# design.net
KiCad netlist of a schematic drawn in Altium Designer
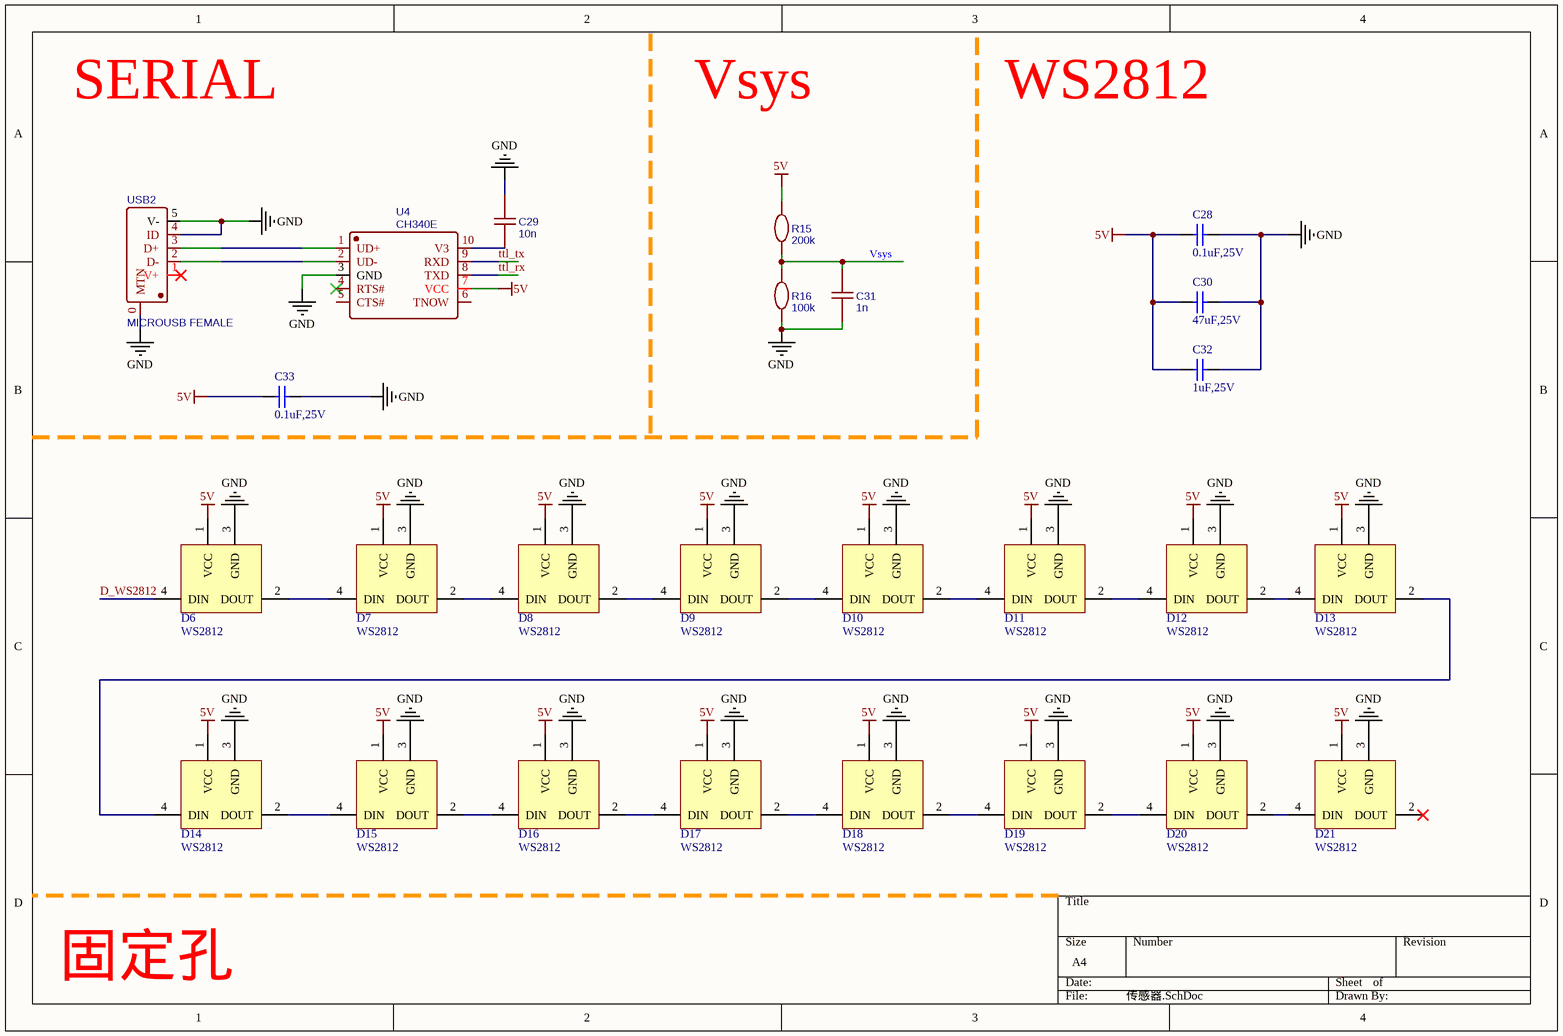
[diagram p0: 传感器.SchDoc]

(export (version "E")
  (design (tool "Eeschema 10.0.6"))
  (components
    (comp (ref "C28")
      (value "0.1uF,25V")
      (footprint "0402_C")
      (description "贴片电容")
      (fields (field (name "PART NUMBER") "T_Cap_0603_0.1uF_25V_X5R") (field (name "TOLERANCE") "10%"))
      (libsource (lib "Database_Library") (part "Cap"))
    )
    (comp (ref "C29")
      (value "10n")
      (footprint "0402_C")
      (fields (field (name "CONTRIBUTOR") "LCEDA_Lib"))
      (libsource (lib "altium-import") (part "root_1_10n_"))
    )
    (comp (ref "C30")
      (value "47uF,25V")
      (footprint "0402_C")
      (description "贴片电容")
      (fields (field (name "PART NUMBER") "T_Cap_0603_0.1uF_25V_X5R") (field (name "TOLERANCE") "10%"))
      (libsource (lib "Database_Library") (part "Cap"))
    )
    (comp (ref "C31")
      (value "1n")
      (footprint "0402_C")
      (fields (field (name "CONTRIBUTOR") "LCEDA_Lib"))
      (libsource (lib "altium-import") (part "root_1_1n_"))
    )
    (comp (ref "C32")
      (value "1uF,25V")
      (footprint "0402_C")
      (description "贴片电容")
      (fields (field (name "PART NUMBER") "T_Cap_0603_0.1uF_25V_X5R") (field (name "TOLERANCE") "10%"))
      (libsource (lib "Database_Library") (part "Cap"))
    )
    (comp (ref "C33")
      (value "0.1uF,25V")
      (footprint "0402_C")
      (description "贴片电容")
      (fields (field (name "PART NUMBER") "T_Cap_0603_0.1uF_25V_X5R") (field (name "TOLERANCE") "10%"))
      (libsource (lib "Database_Library") (part "Cap"))
    )
    (comp (ref "D6")
      (value "WS2812")
      (footprint "LED-SMD_4P-L3.5-W3.5-TL_WS2812B")
      (libsource (lib "Schlib_PICO") (part "WS2812"))
    )
    (comp (ref "D7")
      (value "WS2812")
      (footprint "LED-SMD_4P-L3.5-W3.5-TL_WS2812B")
      (libsource (lib "Schlib_PICO") (part "WS2812"))
    )
    (comp (ref "D8")
      (value "WS2812")
      (footprint "LED-SMD_4P-L3.5-W3.5-TL_WS2812B")
      (libsource (lib "Schlib_PICO") (part "WS2812"))
    )
    (comp (ref "D9")
      (value "WS2812")
      (footprint "LED-SMD_4P-L3.5-W3.5-TL_WS2812B")
      (libsource (lib "Schlib_PICO") (part "WS2812"))
    )
    (comp (ref "D10")
      (value "WS2812")
      (footprint "LED-SMD_4P-L3.5-W3.5-TL_WS2812B")
      (libsource (lib "Schlib_PICO") (part "WS2812"))
    )
    (comp (ref "D11")
      (value "WS2812")
      (footprint "LED-SMD_4P-L3.5-W3.5-TL_WS2812B")
      (libsource (lib "Schlib_PICO") (part "WS2812"))
    )
    (comp (ref "D12")
      (value "WS2812")
      (footprint "LED-SMD_4P-L3.5-W3.5-TL_WS2812B")
      (libsource (lib "Schlib_PICO") (part "WS2812"))
    )
    (comp (ref "D13")
      (value "WS2812")
      (footprint "LED-SMD_4P-L3.5-W3.5-TL_WS2812B")
      (libsource (lib "Schlib_PICO") (part "WS2812"))
    )
    (comp (ref "D14")
      (value "WS2812")
      (footprint "LED-SMD_4P-L3.5-W3.5-TL_WS2812B")
      (libsource (lib "Schlib_PICO") (part "WS2812"))
    )
    (comp (ref "D15")
      (value "WS2812")
      (footprint "LED-SMD_4P-L3.5-W3.5-TL_WS2812B")
      (libsource (lib "Schlib_PICO") (part "WS2812"))
    )
    (comp (ref "D16")
      (value "WS2812")
      (footprint "LED-SMD_4P-L3.5-W3.5-TL_WS2812B")
      (libsource (lib "Schlib_PICO") (part "WS2812"))
    )
    (comp (ref "D17")
      (value "WS2812")
      (footprint "LED-SMD_4P-L3.5-W3.5-TL_WS2812B")
      (libsource (lib "Schlib_PICO") (part "WS2812"))
    )
    (comp (ref "D18")
      (value "WS2812")
      (footprint "LED-SMD_4P-L3.5-W3.5-TL_WS2812B")
      (libsource (lib "Schlib_PICO") (part "WS2812"))
    )
    (comp (ref "D19")
      (value "WS2812")
      (footprint "LED-SMD_4P-L3.5-W3.5-TL_WS2812B")
      (libsource (lib "Schlib_PICO") (part "WS2812"))
    )
    (comp (ref "D20")
      (value "WS2812")
      (footprint "LED-SMD_4P-L3.5-W3.5-TL_WS2812B")
      (libsource (lib "Schlib_PICO") (part "WS2812"))
    )
    (comp (ref "D21")
      (value "WS2812")
      (footprint "LED-SMD_4P-L3.5-W3.5-TL_WS2812B")
      (libsource (lib "Schlib_PICO") (part "WS2812"))
    )
    (comp (ref "R15")
      (value "200k")
      (footprint "0402_R")
      (fields (field (name "CONTRIBUTOR") "LCEDA_Lib"))
      (libsource (lib "altium-import") (part "root_1_200k_"))
    )
    (comp (ref "R16")
      (value "100k")
      (footprint "0402_R")
      (fields (field (name "CONTRIBUTOR") "LCEDA_Lib"))
      (libsource (lib "altium-import") (part "root_1_100k_"))
    )
    (comp (ref "U4")
      (value "CH340E")
      (footprint "MSOP-10_L3.0-W3.0-P0.50-LS5.0-BL")
      (fields (field (name "BOM_SUPPLIER PART") "C99652"))
      (libsource (lib "altium-import") (part "root_0_CH340E_"))
    )
    (comp (ref "USB2")
      (value "MICROUSB FEMALE")
      (footprint "USB-B/S_A")
      (fields
        (field (name "BOM_MANUFACTURER PART") "micro USBFemale")
        (field (name "BOM_SUPPLIER PART") "C10418")
      )
      (libsource (lib "altium-import") (part "root_0_mirrored_MICROUSB FEMALE_"))
    )
  )
  (nets
    (net (code "1") (name "/D_WS2812") (class "Default")
      (node (ref "D6") (pin "4") (pinfunction "DIN_4") (pintype "passive"))
    )
    (net (code "2") (name "/Vsys") (class "Default")
      (node (ref "C31") (pin "2") (pinfunction "2_2") (pintype "passive"))
      (node (ref "R15") (pin "1") (pinfunction "1_1") (pintype "passive"))
      (node (ref "R16") (pin "2") (pinfunction "2_2") (pintype "passive"))
    )
    (net (code "3") (name "/ttl_rx") (class "Default")
      (node (ref "U4") (pin "8") (pinfunction "TXD_8") (pintype "passive"))
    )
    (net (code "4") (name "/ttl_tx") (class "Default")
      (node (ref "U4") (pin "9") (pinfunction "RXD_9") (pintype "passive"))
    )
    (net (code "5") (name "5V") (class "Default")
      (node (ref "C28") (pin "2") (pinfunction "2_2") (pintype "passive"))
      (node (ref "C30") (pin "2") (pinfunction "2_2") (pintype "passive"))
      (node (ref "C32") (pin "2") (pinfunction "2_2") (pintype "passive"))
      (node (ref "C33") (pin "2") (pinfunction "2_2") (pintype "passive"))
      (node (ref "D10") (pin "1") (pinfunction "VCC_1") (pintype "passive"))
      (node (ref "D11") (pin "1") (pinfunction "VCC_1") (pintype "passive"))
      (node (ref "D12") (pin "1") (pinfunction "VCC_1") (pintype "passive"))
      (node (ref "D13") (pin "1") (pinfunction "VCC_1") (pintype "passive"))
      (node (ref "D14") (pin "1") (pinfunction "VCC_1") (pintype "passive"))
      (node (ref "D15") (pin "1") (pinfunction "VCC_1") (pintype "passive"))
      (node (ref "D16") (pin "1") (pinfunction "VCC_1") (pintype "passive"))
      (node (ref "D17") (pin "1") (pinfunction "VCC_1") (pintype "passive"))
      (node (ref "D18") (pin "1") (pinfunction "VCC_1") (pintype "passive"))
      (node (ref "D19") (pin "1") (pinfunction "VCC_1") (pintype "passive"))
      (node (ref "D20") (pin "1") (pinfunction "VCC_1") (pintype "passive"))
      (node (ref "D21") (pin "1") (pinfunction "VCC_1") (pintype "passive"))
      (node (ref "D6") (pin "1") (pinfunction "VCC_1") (pintype "passive"))
      (node (ref "D7") (pin "1") (pinfunction "VCC_1") (pintype "passive"))
      (node (ref "D8") (pin "1") (pinfunction "VCC_1") (pintype "passive"))
      (node (ref "D9") (pin "1") (pinfunction "VCC_1") (pintype "passive"))
      (node (ref "R15") (pin "2") (pinfunction "2_2") (pintype "passive"))
      (node (ref "U4") (pin "7") (pinfunction "VCC_7") (pintype "passive"))
    )
    (net (code "6") (name "GND") (class "Default")
      (node (ref "C28") (pin "1") (pinfunction "1_1") (pintype "passive"))
      (node (ref "C29") (pin "2") (pinfunction "2_2") (pintype "passive"))
      (node (ref "C30") (pin "1") (pinfunction "1_1") (pintype "passive"))
      (node (ref "C31") (pin "1") (pinfunction "1_1") (pintype "passive"))
      (node (ref "C32") (pin "1") (pinfunction "1_1") (pintype "passive"))
      (node (ref "C33") (pin "1") (pinfunction "1_1") (pintype "passive"))
      (node (ref "D10") (pin "3") (pinfunction "GND_3") (pintype "passive"))
      (node (ref "D11") (pin "3") (pinfunction "GND_3") (pintype "passive"))
      (node (ref "D12") (pin "3") (pinfunction "GND_3") (pintype "passive"))
      (node (ref "D13") (pin "3") (pinfunction "GND_3") (pintype "passive"))
      (node (ref "D14") (pin "3") (pinfunction "GND_3") (pintype "passive"))
      (node (ref "D15") (pin "3") (pinfunction "GND_3") (pintype "passive"))
      (node (ref "D16") (pin "3") (pinfunction "GND_3") (pintype "passive"))
      (node (ref "D17") (pin "3") (pinfunction "GND_3") (pintype "passive"))
      (node (ref "D18") (pin "3") (pinfunction "GND_3") (pintype "passive"))
      (node (ref "D19") (pin "3") (pinfunction "GND_3") (pintype "passive"))
      (node (ref "D20") (pin "3") (pinfunction "GND_3") (pintype "passive"))
      (node (ref "D21") (pin "3") (pinfunction "GND_3") (pintype "passive"))
      (node (ref "D6") (pin "3") (pinfunction "GND_3") (pintype "passive"))
      (node (ref "D7") (pin "3") (pinfunction "GND_3") (pintype "passive"))
      (node (ref "D8") (pin "3") (pinfunction "GND_3") (pintype "passive"))
      (node (ref "D9") (pin "3") (pinfunction "GND_3") (pintype "passive"))
      (node (ref "R16") (pin "1") (pinfunction "1_1") (pintype "passive"))
      (node (ref "U4") (pin "3") (pinfunction "GND_3") (pintype "passive"))
      (node (ref "USB2") (pin "0") (pinfunction "MTN_0") (pintype "passive"))
      (node (ref "USB2") (pin "4") (pinfunction "ID_4") (pintype "passive"))
      (node (ref "USB2") (pin "5") (pinfunction "V-_5") (pintype "passive"))
    )
    (net (code "7") (name "Net-(D6-DOUT)") (class "Default")
      (node (ref "D6") (pin "2") (pinfunction "DOUT_2") (pintype "passive"))
      (node (ref "D7") (pin "4") (pinfunction "DIN_4") (pintype "passive"))
    )
    (net (code "8") (name "Net-(D7-DOUT)") (class "Default")
      (node (ref "D7") (pin "2") (pinfunction "DOUT_2") (pintype "passive"))
      (node (ref "D8") (pin "4") (pinfunction "DIN_4") (pintype "passive"))
    )
    (net (code "9") (name "Net-(D8-DOUT)") (class "Default")
      (node (ref "D8") (pin "2") (pinfunction "DOUT_2") (pintype "passive"))
      (node (ref "D9") (pin "4") (pinfunction "DIN_4") (pintype "passive"))
    )
    (net (code "10") (name "Net-(D10-DIN)") (class "Default")
      (node (ref "D10") (pin "4") (pinfunction "DIN_4") (pintype "passive"))
      (node (ref "D9") (pin "2") (pinfunction "DOUT_2") (pintype "passive"))
    )
    (net (code "11") (name "Net-(D10-DOUT)") (class "Default")
      (node (ref "D10") (pin "2") (pinfunction "DOUT_2") (pintype "passive"))
      (node (ref "D11") (pin "4") (pinfunction "DIN_4") (pintype "passive"))
    )
    (net (code "12") (name "Net-(D11-DOUT)") (class "Default")
      (node (ref "D11") (pin "2") (pinfunction "DOUT_2") (pintype "passive"))
      (node (ref "D12") (pin "4") (pinfunction "DIN_4") (pintype "passive"))
    )
    (net (code "13") (name "Net-(D12-DOUT)") (class "Default")
      (node (ref "D12") (pin "2") (pinfunction "DOUT_2") (pintype "passive"))
      (node (ref "D13") (pin "4") (pinfunction "DIN_4") (pintype "passive"))
    )
    (net (code "14") (name "Net-(D13-DOUT)") (class "Default")
      (node (ref "D13") (pin "2") (pinfunction "DOUT_2") (pintype "passive"))
      (node (ref "D14") (pin "4") (pinfunction "DIN_4") (pintype "passive"))
    )
    (net (code "15") (name "Net-(D14-DOUT)") (class "Default")
      (node (ref "D14") (pin "2") (pinfunction "DOUT_2") (pintype "passive"))
      (node (ref "D15") (pin "4") (pinfunction "DIN_4") (pintype "passive"))
    )
    (net (code "16") (name "Net-(D15-DOUT)") (class "Default")
      (node (ref "D15") (pin "2") (pinfunction "DOUT_2") (pintype "passive"))
      (node (ref "D16") (pin "4") (pinfunction "DIN_4") (pintype "passive"))
    )
    (net (code "17") (name "Net-(D16-DOUT)") (class "Default")
      (node (ref "D16") (pin "2") (pinfunction "DOUT_2") (pintype "passive"))
      (node (ref "D17") (pin "4") (pinfunction "DIN_4") (pintype "passive"))
    )
    (net (code "18") (name "Net-(D17-DOUT)") (class "Default")
      (node (ref "D17") (pin "2") (pinfunction "DOUT_2") (pintype "passive"))
      (node (ref "D18") (pin "4") (pinfunction "DIN_4") (pintype "passive"))
    )
    (net (code "19") (name "Net-(D18-DOUT)") (class "Default")
      (node (ref "D18") (pin "2") (pinfunction "DOUT_2") (pintype "passive"))
      (node (ref "D19") (pin "4") (pinfunction "DIN_4") (pintype "passive"))
    )
    (net (code "20") (name "Net-(D19-DOUT)") (class "Default")
      (node (ref "D19") (pin "2") (pinfunction "DOUT_2") (pintype "passive"))
      (node (ref "D20") (pin "4") (pinfunction "DIN_4") (pintype "passive"))
    )
    (net (code "21") (name "Net-(D20-DOUT)") (class "Default")
      (node (ref "D20") (pin "2") (pinfunction "DOUT_2") (pintype "passive"))
      (node (ref "D21") (pin "4") (pinfunction "DIN_4") (pintype "passive"))
    )
    (net (code "22") (name "Net-(U4-UD+)") (class "Default")
      (node (ref "U4") (pin "1") (pinfunction "UD+_1") (pintype "passive"))
      (node (ref "USB2") (pin "3") (pinfunction "D+_3") (pintype "passive"))
    )
    (net (code "23") (name "Net-(U4-UD-)") (class "Default")
      (node (ref "U4") (pin "2") (pinfunction "UD-_2") (pintype "passive"))
      (node (ref "USB2") (pin "2") (pinfunction "D-_2") (pintype "passive"))
    )
    (net (code "24") (name "Net-(U4-V3)") (class "Default")
      (node (ref "C29") (pin "1") (pinfunction "1_1") (pintype "passive"))
      (node (ref "U4") (pin "10") (pinfunction "V3_10") (pintype "passive"))
    )
    (net (code "25") (name "unconnected-(D21-DOUT-Pad2)") (class "Default")
      (node (ref "D21") (pin "2") (pinfunction "DOUT_2") (pintype "passive+no_connect"))
    )
    (net (code "26") (name "unconnected-(U4-CTS#-Pad5)") (class "Default")
      (node (ref "U4") (pin "5") (pinfunction "CTS#_5") (pintype "passive"))
    )
    (net (code "27") (name "unconnected-(U4-RTS#-Pad4)") (class "Default")
      (node (ref "U4") (pin "4") (pinfunction "RTS#_4") (pintype "passive+no_connect"))
    )
    (net (code "28") (name "unconnected-(U4-TNOW-Pad6)") (class "Default")
      (node (ref "U4") (pin "6") (pinfunction "TNOW_6") (pintype "passive"))
    )
    (net (code "29") (name "unconnected-(USB2-V+-Pad1)") (class "Default")
      (node (ref "USB2") (pin "1") (pinfunction "V+_1") (pintype "passive+no_connect"))
    )
  )
)
